# SCH_Final-project_2026-05-26.net
KiCad netlist of a schematic drawn in EasyEDA
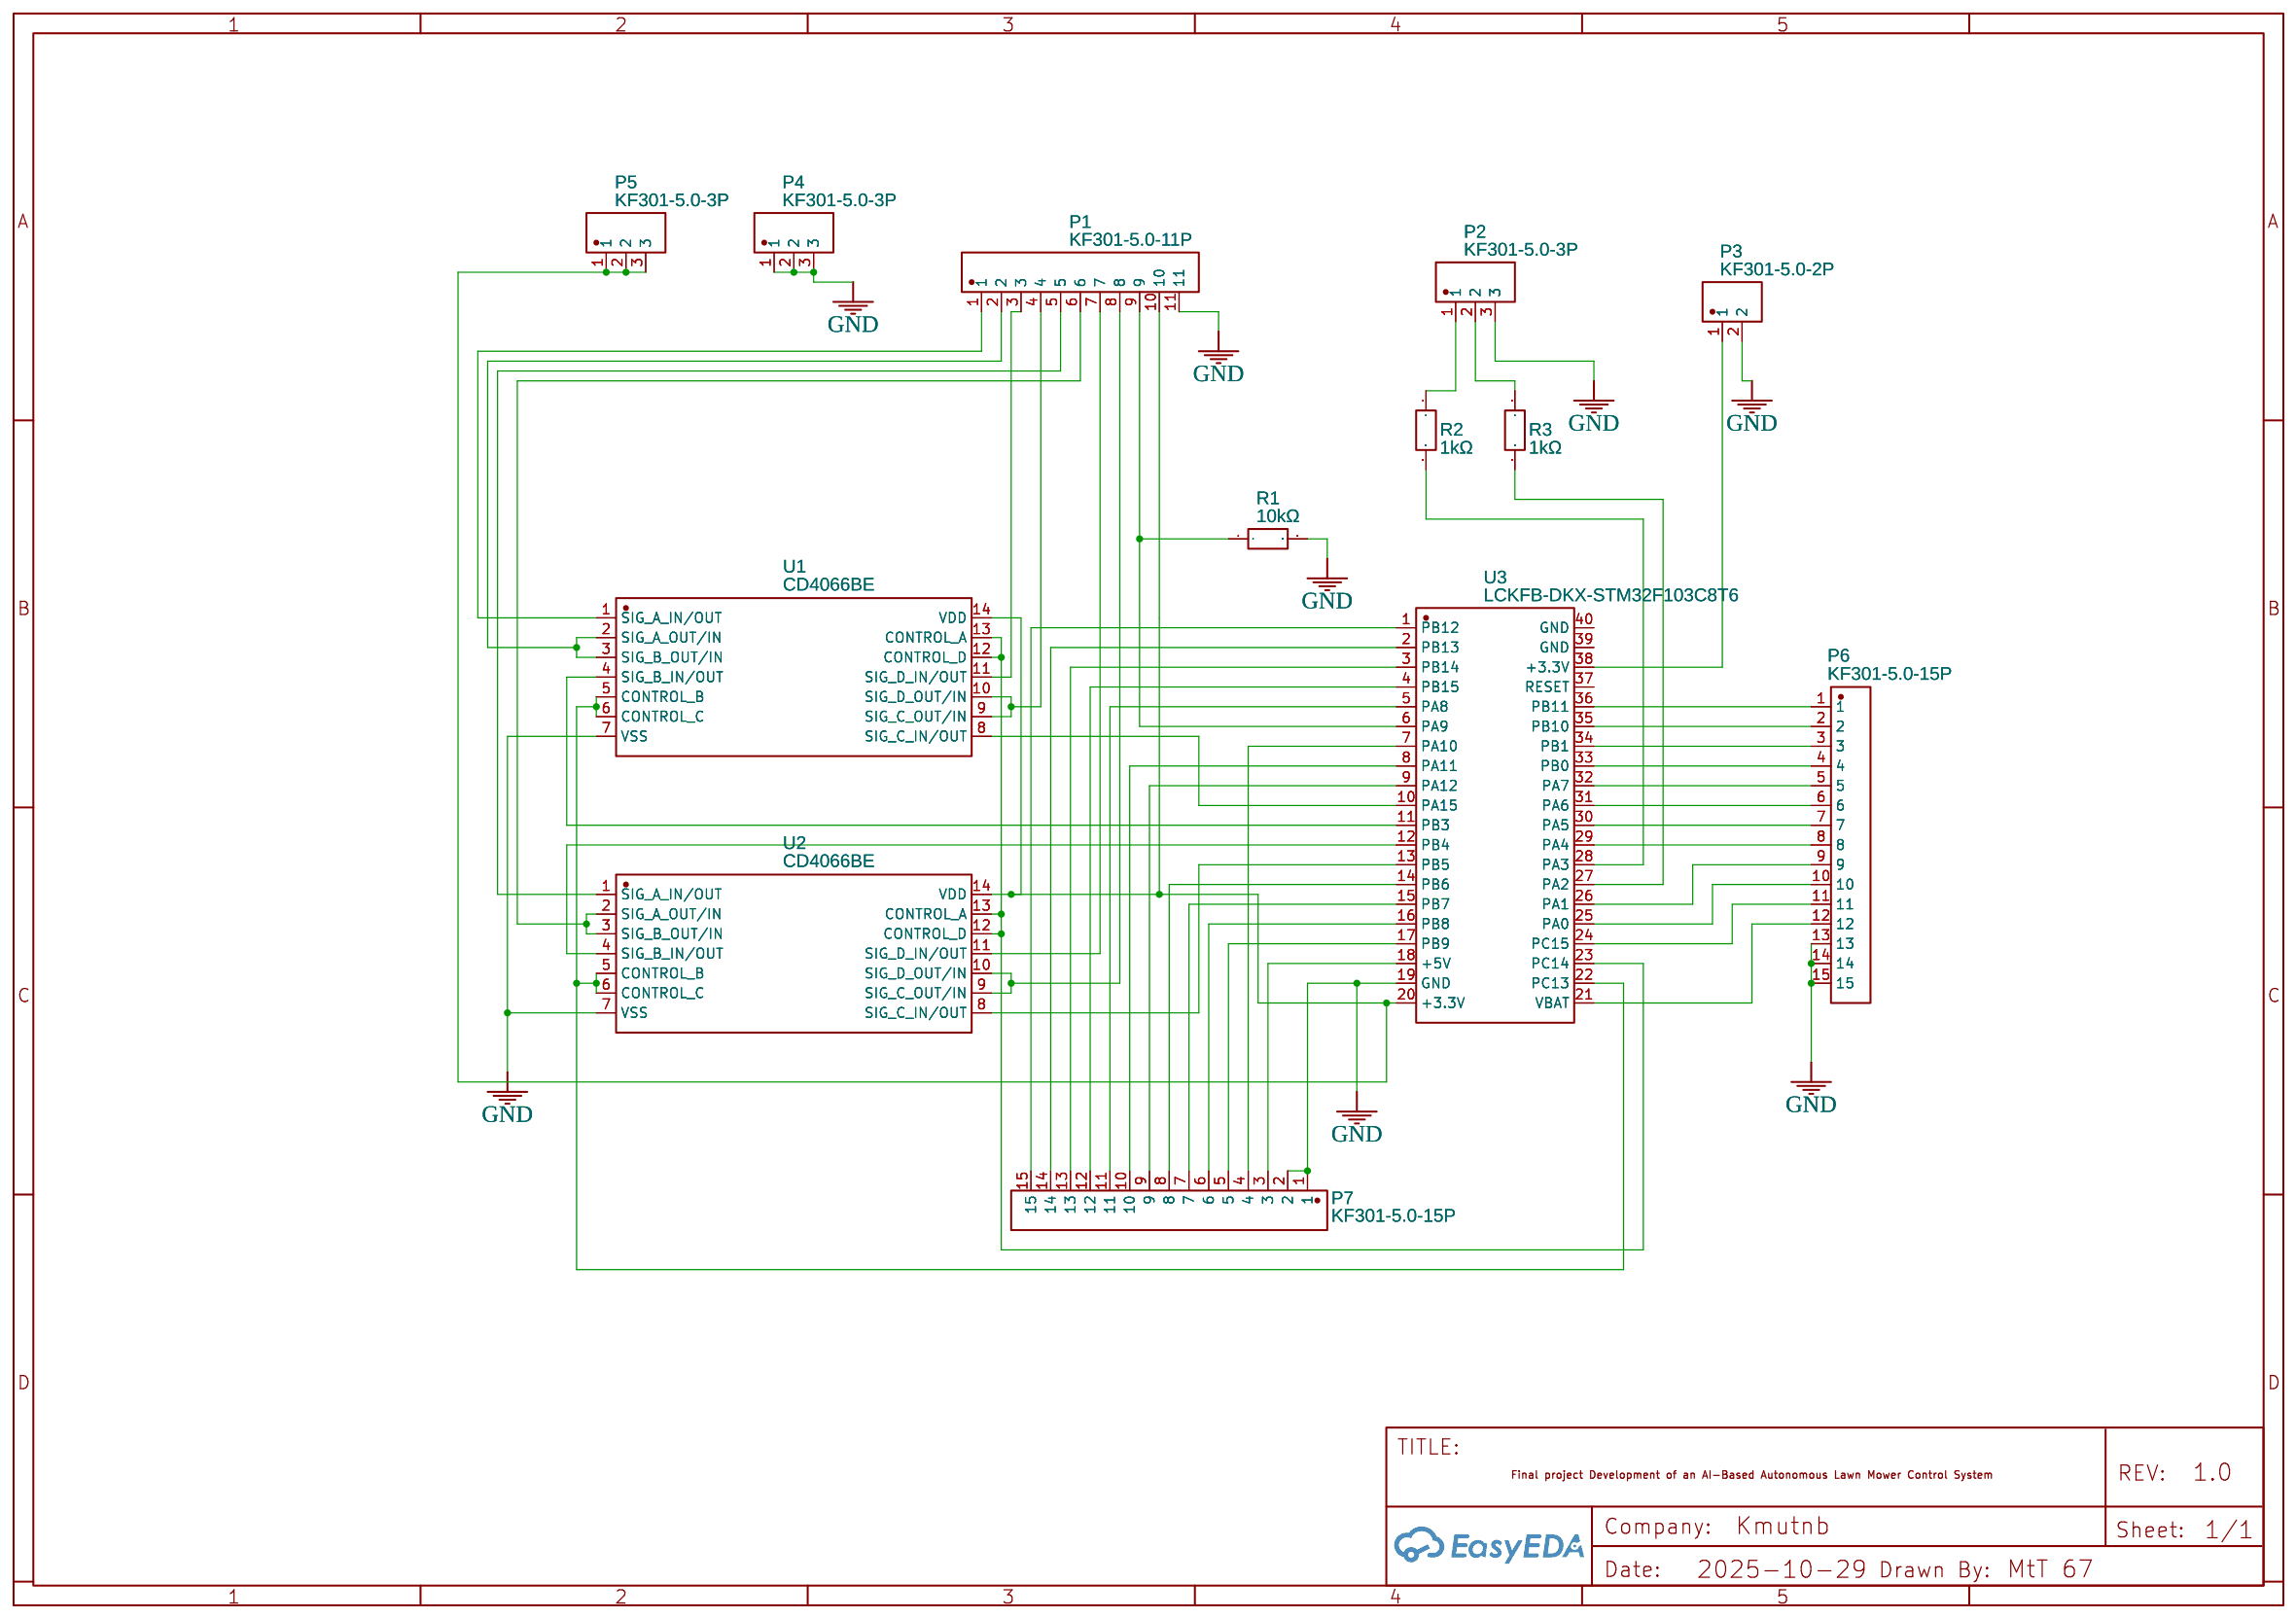
[diagram p0: schematic sheet]

(export (version "E")
  (design (tool "Eeschema 10.0.6"))
  (components
    (comp (ref "P1") (value "KF301-5.0-11P") (libsource (lib "") (part "KF301-5.0-11P")))
    (comp (ref "P2")
      (value "KF301-5.0-3P")
      (fields (field (name "Manufacturer") "KEFA(科发)"))
      (libsource (lib "") (part "KF301-5.0-3P"))
    )
    (comp (ref "P3")
      (value "KF301-5.0-2P")
      (fields (field (name "Manufacturer") "KEFA(科发)"))
      (libsource (lib "") (part "KF301-5.0-2P"))
    )
    (comp (ref "P4")
      (value "KF301-5.0-3P")
      (fields (field (name "Manufacturer") "KEFA(科发)"))
      (libsource (lib "") (part "KF301-5.0-3P"))
    )
    (comp (ref "P5")
      (value "KF301-5.0-3P")
      (fields (field (name "Manufacturer") "KEFA(科发)"))
      (libsource (lib "") (part "KF301-5.0-3P"))
    )
    (comp (ref "P6") (value "KF301-5.0-15P") (libsource (lib "") (part "KF301-5.0-15P")))
    (comp (ref "P7") (value "KF301-5.0-15P") (libsource (lib "") (part "KF301-5.0-15P_1")))
    (comp (ref "R1")
      (value "10kΩ")
      (fields
        (field (name "Manufacturer Part") "RN1/4W10KFT/BA1")
        (field (name "Manufacturer") "Tyohm(幸亚电阻)")
      )
      (libsource (lib "") (part "RN 1/4W 10K F T/B A1_1"))
    )
    (comp (ref "R2")
      (value "1kΩ")
      (fields
        (field (name "Manufacturer Part") "RN1/4W10KFT/BA1")
        (field (name "Manufacturer") "Tyohm(幸亚电阻)")
      )
      (libsource (lib "") (part "RN 1/4W 10K F T/B A1"))
    )
    (comp (ref "R3")
      (value "1kΩ")
      (fields
        (field (name "Manufacturer Part") "RN1/4W10KFT/BA1")
        (field (name "Manufacturer") "Tyohm(幸亚电阻)")
      )
      (libsource (lib "") (part "RN 1/4W 10K F T/B A1"))
    )
    (comp (ref "U1")
      (value "CD4066BE")
      (fields (field (name "Manufacturer") "TI(德州仪器)"))
      (libsource (lib "") (part "CD4066BE"))
    )
    (comp (ref "U2")
      (value "CD4066BE")
      (fields (field (name "Manufacturer") "TI(德州仪器)"))
      (libsource (lib "") (part "CD4066BE"))
    )
    (comp (ref "U3")
      (value "LCKFB-DKX-STM32F103C8T6")
      (fields (field (name "Manufacturer") "立创开发板"))
      (libsource (lib "") (part "LCKFB-DKX-STM32F103C8T6"))
    )
  )
  (nets
    (net (code "1") (name "GND") (class "Default")
      (node (ref "P1") (pin "11") (pinfunction "11_11") (pintype "unspecified"))
      (node (ref "P2") (pin "3") (pinfunction "3_3") (pintype "unspecified"))
      (node (ref "P3") (pin "2") (pinfunction "2_2") (pintype "unspecified"))
      (node (ref "P4") (pin "1") (pinfunction "1_1") (pintype "unspecified"))
      (node (ref "P4") (pin "2") (pinfunction "2_2") (pintype "unspecified"))
      (node (ref "P4") (pin "3") (pinfunction "3_3") (pintype "unspecified"))
      (node (ref "P6") (pin "13") (pinfunction "13_13") (pintype "unspecified"))
      (node (ref "P6") (pin "14") (pinfunction "14_14") (pintype "unspecified"))
      (node (ref "P6") (pin "15") (pinfunction "15_15") (pintype "unspecified"))
      (node (ref "P7") (pin "1") (pinfunction "1_1") (pintype "unspecified"))
      (node (ref "P7") (pin "2") (pinfunction "2_2") (pintype "unspecified"))
      (node (ref "R1") (pin "2") (pinfunction "2_2") (pintype "unspecified"))
      (node (ref "U1") (pin "7") (pinfunction "VSS_7") (pintype "unspecified"))
      (node (ref "U2") (pin "7") (pinfunction "VSS_7") (pintype "unspecified"))
      (node (ref "U3") (pin "19") (pinfunction "GND_19") (pintype "unspecified"))
    )
    (net (code "2") (name "Net-(P2-Pad1)") (class "Default")
      (node (ref "P2") (pin "1") (pinfunction "1_1") (pintype "unspecified"))
      (node (ref "R2") (pin "1") (pinfunction "1_1") (pintype "unspecified"))
    )
    (net (code "3") (name "Net-(P2-Pad2)") (class "Default")
      (node (ref "P2") (pin "2") (pinfunction "2_2") (pintype "unspecified"))
      (node (ref "R3") (pin "1") (pinfunction "1_1") (pintype "unspecified"))
    )
    (net (code "4") (name "Net-(P3-Pad1)") (class "Default")
      (node (ref "P3") (pin "1") (pinfunction "1_1") (pintype "unspecified"))
      (node (ref "U3") (pin "38") (pinfunction "+3.3V_38") (pintype "unspecified"))
    )
    (net (code "5") (name "Net-(U1-CONTROL_A)") (class "Default")
      (node (ref "U1") (pin "12") (pinfunction "CONTROL_D_12") (pintype "unspecified"))
      (node (ref "U1") (pin "13") (pinfunction "CONTROL_A_13") (pintype "unspecified"))
      (node (ref "U2") (pin "12") (pinfunction "CONTROL_D_12") (pintype "unspecified"))
      (node (ref "U2") (pin "13") (pinfunction "CONTROL_A_13") (pintype "unspecified"))
      (node (ref "U3") (pin "23") (pinfunction "PC14_23") (pintype "unspecified"))
    )
    (net (code "6") (name "Net-(U1-CONTROL_B)") (class "Default")
      (node (ref "U1") (pin "5") (pinfunction "CONTROL_B_5") (pintype "unspecified"))
      (node (ref "U1") (pin "6") (pinfunction "CONTROL_C_6") (pintype "unspecified"))
      (node (ref "U2") (pin "5") (pinfunction "CONTROL_B_5") (pintype "unspecified"))
      (node (ref "U2") (pin "6") (pinfunction "CONTROL_C_6") (pintype "unspecified"))
      (node (ref "U3") (pin "22") (pinfunction "PC13_22") (pintype "unspecified"))
    )
    (net (code "7") (name "Net-(U1-SIG_A_IN{slash}OUT)") (class "Default")
      (node (ref "P1") (pin "1") (pinfunction "1_1") (pintype "unspecified"))
      (node (ref "U1") (pin "1") (pinfunction "SIG_A_IN/OUT_1") (pintype "unspecified"))
    )
    (net (code "8") (name "Net-(U1-SIG_A_OUT{slash}IN)") (class "Default")
      (node (ref "P1") (pin "2") (pinfunction "2_2") (pintype "unspecified"))
      (node (ref "U1") (pin "2") (pinfunction "SIG_A_OUT/IN_2") (pintype "unspecified"))
      (node (ref "U1") (pin "3") (pinfunction "SIG_B_OUT/IN_3") (pintype "unspecified"))
    )
    (net (code "9") (name "Net-(U1-SIG_B_IN{slash}OUT)") (class "Default")
      (node (ref "U1") (pin "4") (pinfunction "SIG_B_IN/OUT_4") (pintype "unspecified"))
      (node (ref "U3") (pin "11") (pinfunction "PB3_11") (pintype "unspecified"))
    )
    (net (code "10") (name "Net-(U1-SIG_C_IN{slash}OUT)") (class "Default")
      (node (ref "U1") (pin "8") (pinfunction "SIG_C_IN/OUT_8") (pintype "unspecified"))
      (node (ref "U3") (pin "10") (pinfunction "PA15_10") (pintype "unspecified"))
    )
    (net (code "11") (name "Net-(U1-SIG_C_OUT{slash}IN)") (class "Default")
      (node (ref "P1") (pin "4") (pinfunction "4_4") (pintype "unspecified"))
      (node (ref "U1") (pin "10") (pinfunction "SIG_D_OUT/IN_10") (pintype "unspecified"))
      (node (ref "U1") (pin "9") (pinfunction "SIG_C_OUT/IN_9") (pintype "unspecified"))
    )
    (net (code "12") (name "Net-(U1-SIG_D_IN{slash}OUT)") (class "Default")
      (node (ref "P1") (pin "3") (pinfunction "3_3") (pintype "unspecified"))
      (node (ref "U1") (pin "11") (pinfunction "SIG_D_IN/OUT_11") (pintype "unspecified"))
    )
    (net (code "13") (name "Net-(U1-VDD)") (class "Default")
      (node (ref "P1") (pin "10") (pinfunction "10_10") (pintype "unspecified"))
      (node (ref "P5") (pin "1") (pinfunction "1_1") (pintype "unspecified"))
      (node (ref "P5") (pin "2") (pinfunction "2_2") (pintype "unspecified"))
      (node (ref "P5") (pin "3") (pinfunction "3_3") (pintype "unspecified"))
      (node (ref "U1") (pin "14") (pinfunction "VDD_14") (pintype "unspecified"))
      (node (ref "U2") (pin "14") (pinfunction "VDD_14") (pintype "unspecified"))
      (node (ref "U3") (pin "20") (pinfunction "+3.3V_20") (pintype "unspecified"))
    )
    (net (code "14") (name "Net-(U2-SIG_A_IN{slash}OUT)") (class "Default")
      (node (ref "P1") (pin "5") (pinfunction "5_5") (pintype "unspecified"))
      (node (ref "U2") (pin "1") (pinfunction "SIG_A_IN/OUT_1") (pintype "unspecified"))
    )
    (net (code "15") (name "Net-(U2-SIG_A_OUT{slash}IN)") (class "Default")
      (node (ref "P1") (pin "6") (pinfunction "6_6") (pintype "unspecified"))
      (node (ref "U2") (pin "2") (pinfunction "SIG_A_OUT/IN_2") (pintype "unspecified"))
      (node (ref "U2") (pin "3") (pinfunction "SIG_B_OUT/IN_3") (pintype "unspecified"))
    )
    (net (code "16") (name "Net-(U2-SIG_B_IN{slash}OUT)") (class "Default")
      (node (ref "U2") (pin "4") (pinfunction "SIG_B_IN/OUT_4") (pintype "unspecified"))
      (node (ref "U3") (pin "12") (pinfunction "PB4_12") (pintype "unspecified"))
    )
    (net (code "17") (name "Net-(U2-SIG_C_IN{slash}OUT)") (class "Default")
      (node (ref "U2") (pin "8") (pinfunction "SIG_C_IN/OUT_8") (pintype "unspecified"))
      (node (ref "U3") (pin "13") (pinfunction "PB5_13") (pintype "unspecified"))
    )
    (net (code "18") (name "Net-(U2-SIG_C_OUT{slash}IN)") (class "Default")
      (node (ref "P1") (pin "8") (pinfunction "8_8") (pintype "unspecified"))
      (node (ref "U2") (pin "10") (pinfunction "SIG_D_OUT/IN_10") (pintype "unspecified"))
      (node (ref "U2") (pin "9") (pinfunction "SIG_C_OUT/IN_9") (pintype "unspecified"))
    )
    (net (code "19") (name "Net-(U2-SIG_D_IN{slash}OUT)") (class "Default")
      (node (ref "P1") (pin "7") (pinfunction "7_7") (pintype "unspecified"))
      (node (ref "U2") (pin "11") (pinfunction "SIG_D_IN/OUT_11") (pintype "unspecified"))
    )
    (net (code "20") (name "Net-(U3-+5V)") (class "Default")
      (node (ref "P7") (pin "3") (pinfunction "3_3") (pintype "unspecified"))
      (node (ref "U3") (pin "18") (pinfunction "+5V_18") (pintype "unspecified"))
    )
    (net (code "21") (name "Net-(U3-PA0)") (class "Default")
      (node (ref "P6") (pin "10") (pinfunction "10_10") (pintype "unspecified"))
      (node (ref "U3") (pin "25") (pinfunction "PA0_25") (pintype "unspecified"))
    )
    (net (code "22") (name "Net-(U3-PA1)") (class "Default")
      (node (ref "P6") (pin "9") (pinfunction "9_9") (pintype "unspecified"))
      (node (ref "U3") (pin "26") (pinfunction "PA1_26") (pintype "unspecified"))
    )
    (net (code "23") (name "Net-(U3-PA2)") (class "Default")
      (node (ref "R3") (pin "2") (pinfunction "2_2") (pintype "unspecified"))
      (node (ref "U3") (pin "27") (pinfunction "PA2_27") (pintype "unspecified"))
    )
    (net (code "24") (name "Net-(U3-PA3)") (class "Default")
      (node (ref "R2") (pin "2") (pinfunction "2_2") (pintype "unspecified"))
      (node (ref "U3") (pin "28") (pinfunction "PA3_28") (pintype "unspecified"))
    )
    (net (code "25") (name "Net-(U3-PA4)") (class "Default")
      (node (ref "P6") (pin "8") (pinfunction "8_8") (pintype "unspecified"))
      (node (ref "U3") (pin "29") (pinfunction "PA4_29") (pintype "unspecified"))
    )
    (net (code "26") (name "Net-(U3-PA5)") (class "Default")
      (node (ref "P6") (pin "7") (pinfunction "7_7") (pintype "unspecified"))
      (node (ref "U3") (pin "30") (pinfunction "PA5_30") (pintype "unspecified"))
    )
    (net (code "27") (name "Net-(U3-PA6)") (class "Default")
      (node (ref "P6") (pin "6") (pinfunction "6_6") (pintype "unspecified"))
      (node (ref "U3") (pin "31") (pinfunction "PA6_31") (pintype "unspecified"))
    )
    (net (code "28") (name "Net-(U3-PA7)") (class "Default")
      (node (ref "P6") (pin "5") (pinfunction "5_5") (pintype "unspecified"))
      (node (ref "U3") (pin "32") (pinfunction "PA7_32") (pintype "unspecified"))
    )
    (net (code "29") (name "Net-(U3-PA8)") (class "Default")
      (node (ref "P7") (pin "11") (pinfunction "11_11") (pintype "unspecified"))
      (node (ref "U3") (pin "5") (pinfunction "PA8_5") (pintype "unspecified"))
    )
    (net (code "30") (name "Net-(U3-PA9)") (class "Default")
      (node (ref "P1") (pin "9") (pinfunction "9_9") (pintype "unspecified"))
      (node (ref "R1") (pin "1") (pinfunction "1_1") (pintype "unspecified"))
      (node (ref "U3") (pin "6") (pinfunction "PA9_6") (pintype "unspecified"))
    )
    (net (code "31") (name "Net-(U3-PA10)") (class "Default")
      (node (ref "P7") (pin "4") (pinfunction "4_4") (pintype "unspecified"))
      (node (ref "U3") (pin "7") (pinfunction "PA10_7") (pintype "unspecified"))
    )
    (net (code "32") (name "Net-(U3-PA11)") (class "Default")
      (node (ref "P7") (pin "10") (pinfunction "10_10") (pintype "unspecified"))
      (node (ref "U3") (pin "8") (pinfunction "PA11_8") (pintype "unspecified"))
    )
    (net (code "33") (name "Net-(U3-PA12)") (class "Default")
      (node (ref "P7") (pin "9") (pinfunction "9_9") (pintype "unspecified"))
      (node (ref "U3") (pin "9") (pinfunction "PA12_9") (pintype "unspecified"))
    )
    (net (code "34") (name "Net-(U3-PB0)") (class "Default")
      (node (ref "P6") (pin "4") (pinfunction "4_4") (pintype "unspecified"))
      (node (ref "U3") (pin "33") (pinfunction "PB0_33") (pintype "unspecified"))
    )
    (net (code "35") (name "Net-(U3-PB1)") (class "Default")
      (node (ref "P6") (pin "3") (pinfunction "3_3") (pintype "unspecified"))
      (node (ref "U3") (pin "34") (pinfunction "PB1_34") (pintype "unspecified"))
    )
    (net (code "36") (name "Net-(U3-PB6)") (class "Default")
      (node (ref "P7") (pin "8") (pinfunction "8_8") (pintype "unspecified"))
      (node (ref "U3") (pin "14") (pinfunction "PB6_14") (pintype "unspecified"))
    )
    (net (code "37") (name "Net-(U3-PB7)") (class "Default")
      (node (ref "P7") (pin "7") (pinfunction "7_7") (pintype "unspecified"))
      (node (ref "U3") (pin "15") (pinfunction "PB7_15") (pintype "unspecified"))
    )
    (net (code "38") (name "Net-(U3-PB8)") (class "Default")
      (node (ref "P7") (pin "6") (pinfunction "6_6") (pintype "unspecified"))
      (node (ref "U3") (pin "16") (pinfunction "PB8_16") (pintype "unspecified"))
    )
    (net (code "39") (name "Net-(U3-PB9)") (class "Default")
      (node (ref "P7") (pin "5") (pinfunction "5_5") (pintype "unspecified"))
      (node (ref "U3") (pin "17") (pinfunction "PB9_17") (pintype "unspecified"))
    )
    (net (code "40") (name "Net-(U3-PB10)") (class "Default")
      (node (ref "P6") (pin "2") (pinfunction "2_2") (pintype "unspecified"))
      (node (ref "U3") (pin "35") (pinfunction "PB10_35") (pintype "unspecified"))
    )
    (net (code "41") (name "Net-(U3-PB11)") (class "Default")
      (node (ref "P6") (pin "1") (pinfunction "1_1") (pintype "unspecified"))
      (node (ref "U3") (pin "36") (pinfunction "PB11_36") (pintype "unspecified"))
    )
    (net (code "42") (name "Net-(U3-PB12)") (class "Default")
      (node (ref "P7") (pin "15") (pinfunction "15_15") (pintype "unspecified"))
      (node (ref "U3") (pin "1") (pinfunction "PB12_1") (pintype "unspecified"))
    )
    (net (code "43") (name "Net-(U3-PB13)") (class "Default")
      (node (ref "P7") (pin "14") (pinfunction "14_14") (pintype "unspecified"))
      (node (ref "U3") (pin "2") (pinfunction "PB13_2") (pintype "unspecified"))
    )
    (net (code "44") (name "Net-(U3-PB14)") (class "Default")
      (node (ref "P7") (pin "13") (pinfunction "13_13") (pintype "unspecified"))
      (node (ref "U3") (pin "3") (pinfunction "PB14_3") (pintype "unspecified"))
    )
    (net (code "45") (name "Net-(U3-PB15)") (class "Default")
      (node (ref "P7") (pin "12") (pinfunction "12_12") (pintype "unspecified"))
      (node (ref "U3") (pin "4") (pinfunction "PB15_4") (pintype "unspecified"))
    )
    (net (code "46") (name "Net-(U3-PC15)") (class "Default")
      (node (ref "P6") (pin "11") (pinfunction "11_11") (pintype "unspecified"))
      (node (ref "U3") (pin "24") (pinfunction "PC15_24") (pintype "unspecified"))
    )
    (net (code "47") (name "Net-(U3-VBAT)") (class "Default")
      (node (ref "P6") (pin "12") (pinfunction "12_12") (pintype "unspecified"))
      (node (ref "U3") (pin "21") (pinfunction "VBAT_21") (pintype "unspecified"))
    )
    (net (code "48") (name "unconnected-(U3-GND-Pad39)") (class "Default")
      (node (ref "U3") (pin "39") (pinfunction "GND_39") (pintype "unspecified"))
    )
    (net (code "49") (name "unconnected-(U3-GND-Pad40)") (class "Default")
      (node (ref "U3") (pin "40") (pinfunction "GND_40") (pintype "unspecified"))
    )
    (net (code "50") (name "unconnected-(U3-RESET-Pad37)") (class "Default")
      (node (ref "U3") (pin "37") (pinfunction "RESET_37") (pintype "unspecified"))
    )
  )
)
